# DAC.net
KiCad netlist of a schematic drawn in Altium Designer
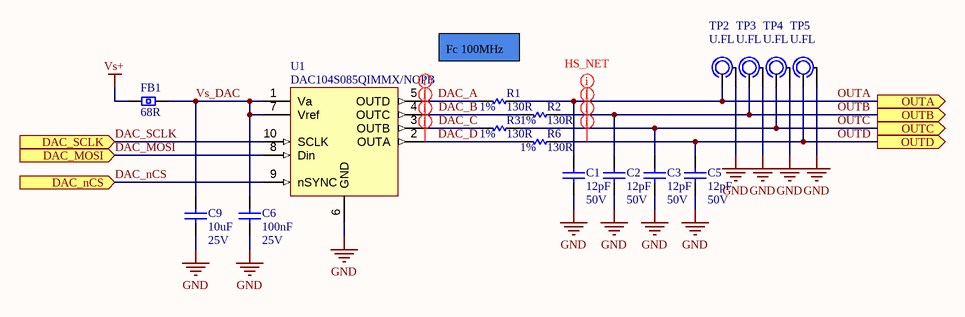
[diagram p0: DAC.SchDoc]

(export (version "E")
  (design (tool "Eeschema 10.0.6"))
  (components
    (comp (ref "C1")
      (value "12pF")
      (footprint "C0402")
      (description "Ceramic capacitor SMD-0402 12pF /50V C0G# J +-5%, Samsung, RoHS")
      (fields
        (field (name "MANUFACTURER") "Samsung")
        (field (name "MANUFACTURER PART NUMBER") "CL05C120JB5NNNC")
        (field (name "VOLTAGE") "50V")
      )
      (libsource (lib "LaserDiode_Analog") (part "CAP CER 12pF 50V C0G 0402"))
    )
    (comp (ref "C2")
      (value "12pF")
      (footprint "C0402")
      (description "Ceramic capacitor SMD-0402 12pF /50V C0G# J +-5%, Samsung, RoHS")
      (fields
        (field (name "MANUFACTURER") "Samsung")
        (field (name "MANUFACTURER PART NUMBER") "CL05C120JB5NNNC")
        (field (name "VOLTAGE") "50V")
      )
      (libsource (lib "LaserDiode_Analog") (part "CAP CER 12pF 50V C0G 0402"))
    )
    (comp (ref "C3")
      (value "12pF")
      (footprint "C0402")
      (description "Ceramic capacitor SMD-0402 12pF /50V C0G# J +-5%, Samsung, RoHS")
      (fields
        (field (name "MANUFACTURER") "Samsung")
        (field (name "MANUFACTURER PART NUMBER") "CL05C120JB5NNNC")
        (field (name "VOLTAGE") "50V")
      )
      (libsource (lib "LaserDiode_Analog") (part "CAP CER 12pF 50V C0G 0402"))
    )
    (comp (ref "C5")
      (value "12pF")
      (footprint "C0402")
      (description "Ceramic capacitor SMD-0402 12pF /50V C0G# J +-5%, Samsung, RoHS")
      (fields
        (field (name "MANUFACTURER") "Samsung")
        (field (name "MANUFACTURER PART NUMBER") "CL05C120JB5NNNC")
        (field (name "VOLTAGE") "50V")
      )
      (libsource (lib "LaserDiode_Analog") (part "CAP CER 12pF 50V C0G 0402"))
    )
    (comp (ref "C6")
      (value "100nF")
      (footprint "C0402")
      (description "Cap Ceramic 0.1uF 25V X5R 10% Pad SMD 0402 85°C T/R / Multi Layer Ceramic Capacitor (MLCC)")
      (fields
        (field (name "MANUFACTURER") "Samsung")
        (field (name "MANUFACTURER PART NUMBER") "CL05A104KA5NNNC")
        (field (name "VOLTAGE RATING") "25V")
      )
      (libsource (lib "OPAMP_DEV_SOT5_6-23") (part "CAP CER 100nF 25V X5R 0402"))
    )
    (comp (ref "C9")
      (value "10uF")
      (footprint "c0805")
      (description "Cap Ceramic 10uF 25V X5R 10% SMD 0805 85°C Embossed T/R")
      (fields
        (field (name "MANUFACTURER") "Samsung")
        (field (name "MANUFACTURER PART NUMBER") "CL21A106KAYNNNE")
        (field (name "VOLTAGE RATING") "25V")
      )
      (libsource (lib "OPAMP_DEV_SOT5_6-23") (part "CAP CER 10uF 25V X5R 0805"))
    )
    (comp (ref "FB1")
      (value "68R")
      (footprint "FB0402")
      (description "Ferrite Beads Multi-Layer 68Ohm 25% 100MHz 400mA 310mOhm DCR 0402 T/R")
      (fields
        (field (name "MANUFACTURER") "Taiyo Yuden")
        (field (name "MANUFACTURER PART NUMBER") "BK1005LL680-T")
      )
      (libsource (lib "MCU") (part "FB 68R 400mA 310mR 0402"))
    )
    (comp (ref "R1")
      (value "130R")
      (footprint "R0402")
      (description "Res General Purpose Thick Film 0402 130 Ohm 1% 1/16W ±100ppm/°C Molded SMD Paper T/R")
      (fields (field (name "TOLERANCE") "1%"))
      (libsource (lib "LaserDiode_Analog") (part "RES 130R 1% 63mW 0402"))
    )
    (comp (ref "R2")
      (value "130R")
      (footprint "R0402")
      (description "Res General Purpose Thick Film 0402 130 Ohm 1% 1/16W ±100ppm/°C Molded SMD Paper T/R")
      (fields (field (name "TOLERANCE") "1%"))
      (libsource (lib "LaserDiode_Analog") (part "RES 130R 1% 63mW 0402"))
    )
    (comp (ref "R3")
      (value "130R")
      (footprint "R0402")
      (description "Res General Purpose Thick Film 0402 130 Ohm 1% 1/16W ±100ppm/°C Molded SMD Paper T/R")
      (fields (field (name "TOLERANCE") "1%"))
      (libsource (lib "LaserDiode_Analog") (part "RES 130R 1% 63mW 0402"))
    )
    (comp (ref "R6")
      (value "130R")
      (footprint "R0402")
      (description "Res General Purpose Thick Film 0402 130 Ohm 1% 1/16W ±100ppm/°C Molded SMD Paper T/R")
      (fields (field (name "TOLERANCE") "1%"))
      (libsource (lib "LaserDiode_Analog") (part "RES 130R 1% 63mW 0402"))
    )
    (comp (ref "TP2")
      (value "U.FL")
      (footprint "U.FL")
      (description "CONN U.FL RCPT STR 50 OHM SMD")
      (fields
        (field (name "MANUFACTURER") "Hirose")
        (field (name "MANUFACTURER PART NUMBER") "U.FL-R-SMT-1(80)")
      )
      (libsource (lib "OPAMP_DEV_SOT5_6-23") (part "TP U.FL"))
    )
    (comp (ref "TP3")
      (value "U.FL")
      (footprint "U.FL")
      (description "CONN U.FL RCPT STR 50 OHM SMD")
      (fields
        (field (name "MANUFACTURER") "Hirose")
        (field (name "MANUFACTURER PART NUMBER") "U.FL-R-SMT-1(80)")
      )
      (libsource (lib "OPAMP_DEV_SOT5_6-23") (part "TP U.FL"))
    )
    (comp (ref "TP4")
      (value "U.FL")
      (footprint "U.FL")
      (description "CONN U.FL RCPT STR 50 OHM SMD")
      (fields
        (field (name "MANUFACTURER") "Hirose")
        (field (name "MANUFACTURER PART NUMBER") "U.FL-R-SMT-1(80)")
      )
      (libsource (lib "OPAMP_DEV_SOT5_6-23") (part "TP U.FL"))
    )
    (comp (ref "TP5")
      (value "U.FL")
      (footprint "U.FL")
      (description "CONN U.FL RCPT STR 50 OHM SMD")
      (fields
        (field (name "MANUFACTURER") "Hirose")
        (field (name "MANUFACTURER PART NUMBER") "U.FL-R-SMT-1(80)")
      )
      (libsource (lib "OPAMP_DEV_SOT5_6-23") (part "TP U.FL"))
    )
    (comp (ref "U1")
      (value "DAC104S085QIMMX/NOPB")
      (footprint "TSSOP50P490X110-10N")
      (description "DAC 4-CH Resistor-String 10-bit Automotive 10-Pin VSSOP T/R")
      (libsource (lib "LaserDiode_Analog") (part "IC DAC 10b 4chan DAC104S085QIMMX/NOPB"))
    )
  )
  (nets
    (net (code "1") (name "/DAC_A") (class "Default")
      (node (ref "R1") (pin "2") (pinfunction "2_2") (pintype "passive"))
      (node (ref "U1") (pin "5") (pinfunction "OUTD_5") (pintype "output"))
    )
    (net (code "2") (name "/DAC_B") (class "Default")
      (node (ref "R2") (pin "2") (pinfunction "2_2") (pintype "passive"))
      (node (ref "U1") (pin "4") (pinfunction "OUTC_4") (pintype "output"))
    )
    (net (code "3") (name "/DAC_C") (class "Default")
      (node (ref "R3") (pin "2") (pinfunction "2_2") (pintype "passive"))
      (node (ref "U1") (pin "3") (pinfunction "OUTB_3") (pintype "output"))
    )
    (net (code "4") (name "/DAC_D") (class "Default")
      (node (ref "R6") (pin "2") (pinfunction "2_2") (pintype "passive"))
      (node (ref "U1") (pin "2") (pinfunction "OUTA_2") (pintype "output"))
    )
    (net (code "5") (name "/DAC_MOSI") (class "Default")
      (node (ref "U1") (pin "8") (pinfunction "Din_8") (pintype "input"))
    )
    (net (code "6") (name "/DAC_SCLK") (class "Default")
      (node (ref "U1") (pin "10") (pinfunction "SCLK_10") (pintype "input"))
    )
    (net (code "7") (name "/DAC_nCS") (class "Default")
      (node (ref "U1") (pin "9") (pinfunction "nSYNC_9") (pintype "input"))
    )
    (net (code "8") (name "/OUTA") (class "Default")
      (node (ref "C1") (pin "2") (pinfunction "2_2") (pintype "passive"))
      (node (ref "R1") (pin "1") (pinfunction "1_1") (pintype "passive"))
      (node (ref "TP2") (pin "1") (pinfunction "1_1") (pintype "passive"))
    )
    (net (code "9") (name "/OUTB") (class "Default")
      (node (ref "C2") (pin "2") (pinfunction "2_2") (pintype "passive"))
      (node (ref "R2") (pin "1") (pinfunction "1_1") (pintype "passive"))
      (node (ref "TP3") (pin "1") (pinfunction "1_1") (pintype "passive"))
    )
    (net (code "10") (name "/OUTC") (class "Default")
      (node (ref "C3") (pin "2") (pinfunction "2_2") (pintype "passive"))
      (node (ref "R3") (pin "1") (pinfunction "1_1") (pintype "passive"))
      (node (ref "TP4") (pin "1") (pinfunction "1_1") (pintype "passive"))
    )
    (net (code "11") (name "/OUTD") (class "Default")
      (node (ref "C5") (pin "2") (pinfunction "2_2") (pintype "passive"))
      (node (ref "R6") (pin "1") (pinfunction "1_1") (pintype "passive"))
      (node (ref "TP5") (pin "1") (pinfunction "1_1") (pintype "passive"))
    )
    (net (code "12") (name "/Vs_DAC") (class "Default")
      (node (ref "C6") (pin "1") (pinfunction "1_1") (pintype "passive"))
      (node (ref "C9") (pin "2") (pinfunction "2_2") (pintype "passive"))
      (node (ref "FB1") (pin "1") (pintype "passive"))
      (node (ref "U1") (pin "1") (pinfunction "Va_1") (pintype "power_in"))
      (node (ref "U1") (pin "7") (pinfunction "Vref_7") (pintype "power_in"))
    )
    (net (code "13") (name "GND") (class "Default")
      (node (ref "C1") (pin "1") (pinfunction "1_1") (pintype "passive"))
      (node (ref "C2") (pin "1") (pinfunction "1_1") (pintype "passive"))
      (node (ref "C3") (pin "1") (pinfunction "1_1") (pintype "passive"))
      (node (ref "C5") (pin "1") (pinfunction "1_1") (pintype "passive"))
      (node (ref "C6") (pin "2") (pinfunction "2_2") (pintype "passive"))
      (node (ref "C9") (pin "1") (pinfunction "1_1") (pintype "passive"))
      (node (ref "TP2") (pin "0") (pinfunction "0_0") (pintype "passive"))
      (node (ref "TP3") (pin "0") (pinfunction "0_0") (pintype "passive"))
      (node (ref "TP4") (pin "0") (pinfunction "0_0") (pintype "passive"))
      (node (ref "TP5") (pin "0") (pinfunction "0_0") (pintype "passive"))
      (node (ref "U1") (pin "6") (pinfunction "GND_6") (pintype "power_in"))
    )
    (net (code "14") (name "Vs+") (class "Default") (node (ref "FB1") (pin "2") (pintype "passive")))
  )
)
